# S111F.net
KiCad netlist of a schematic drawn in EAGLE
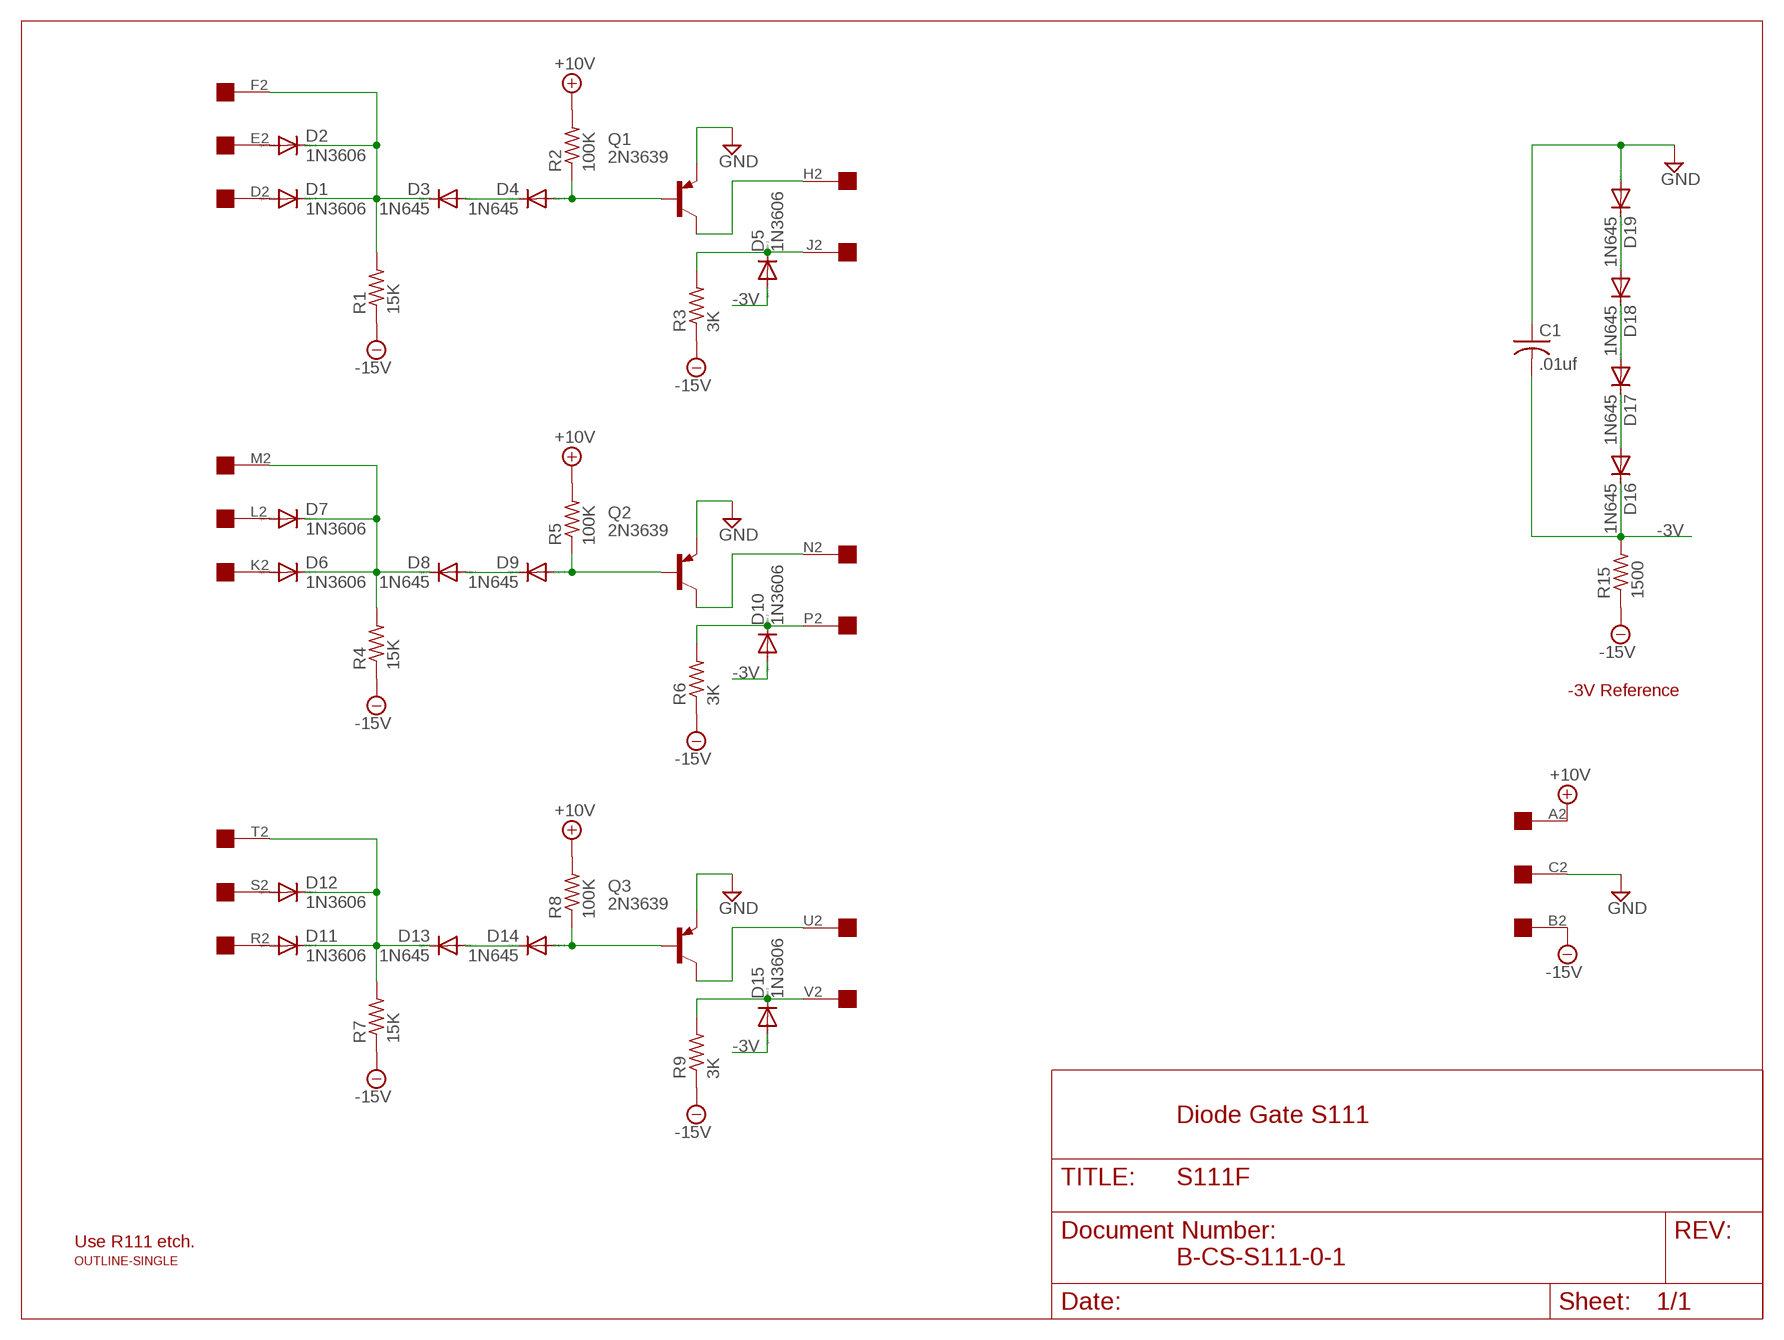
[diagram p0: schematic, sheet 1]

(export (version "E")
  (design (tool "Eeschema 10.0.6"))
  (components
    (comp (ref "C1")
      (value ".01uf")
      (footprint "eagle-import:C050-025X075")
      (libsource (lib "eagle-import") (part "C-US050-025X075"))
    )
    (comp (ref "D1")
      (value "1N3606")
      (footprint "eagle-import:DO35-10")
      (libsource (lib "eagle-import") (part "1N4148DO35-10"))
    )
    (comp (ref "D2")
      (value "1N3606")
      (footprint "eagle-import:DO35-10")
      (libsource (lib "eagle-import") (part "1N4148DO35-10"))
    )
    (comp (ref "D3")
      (value "1N645")
      (footprint "eagle-import:DO35-10")
      (libsource (lib "eagle-import") (part "1N4148DO35-10"))
    )
    (comp (ref "D4")
      (value "1N645")
      (footprint "eagle-import:DO35-10")
      (libsource (lib "eagle-import") (part "1N4148DO35-10"))
    )
    (comp (ref "D5")
      (value "1N3606")
      (footprint "eagle-import:DO35-10")
      (libsource (lib "eagle-import") (part "1N4148DO35-10"))
    )
    (comp (ref "D6")
      (value "1N3606")
      (footprint "eagle-import:DO35-10")
      (libsource (lib "eagle-import") (part "1N4148DO35-10"))
    )
    (comp (ref "D7")
      (value "1N3606")
      (footprint "eagle-import:DO35-10")
      (libsource (lib "eagle-import") (part "1N4148DO35-10"))
    )
    (comp (ref "D8")
      (value "1N645")
      (footprint "eagle-import:DO35-10")
      (libsource (lib "eagle-import") (part "1N4148DO35-10"))
    )
    (comp (ref "D9")
      (value "1N645")
      (footprint "eagle-import:DO35-10")
      (libsource (lib "eagle-import") (part "1N4148DO35-10"))
    )
    (comp (ref "D10")
      (value "1N3606")
      (footprint "eagle-import:DO35-10")
      (libsource (lib "eagle-import") (part "1N4148DO35-10"))
    )
    (comp (ref "D11")
      (value "1N3606")
      (footprint "eagle-import:DO35-10")
      (libsource (lib "eagle-import") (part "1N4148DO35-10"))
    )
    (comp (ref "D12")
      (value "1N3606")
      (footprint "eagle-import:DO35-10")
      (libsource (lib "eagle-import") (part "1N4148DO35-10"))
    )
    (comp (ref "D13")
      (value "1N645")
      (footprint "eagle-import:DO35-10")
      (libsource (lib "eagle-import") (part "1N4148DO35-10"))
    )
    (comp (ref "D14")
      (value "1N645")
      (footprint "eagle-import:DO35-10")
      (libsource (lib "eagle-import") (part "1N4148DO35-10"))
    )
    (comp (ref "D15")
      (value "1N3606")
      (footprint "eagle-import:DO35-10")
      (libsource (lib "eagle-import") (part "1N4148DO35-10"))
    )
    (comp (ref "D16")
      (value "1N645")
      (footprint "eagle-import:DO35-10")
      (libsource (lib "eagle-import") (part "1N4148DO35-10"))
    )
    (comp (ref "D17")
      (value "1N645")
      (footprint "eagle-import:DO35-10")
      (libsource (lib "eagle-import") (part "1N4148DO35-10"))
    )
    (comp (ref "D18")
      (value "1N645")
      (footprint "eagle-import:DO35-10")
      (libsource (lib "eagle-import") (part "1N4148DO35-10"))
    )
    (comp (ref "D19")
      (value "1N645")
      (footprint "eagle-import:DO35-10")
      (libsource (lib "eagle-import") (part "1N4148DO35-10"))
    )
    (comp (ref "Q1")
      (value "2N3639")
      (footprint "eagle-import:TO39")
      (libsource (lib "eagle-import") (part "2N3637"))
    )
    (comp (ref "Q2")
      (value "2N3639")
      (footprint "eagle-import:TO39")
      (libsource (lib "eagle-import") (part "2N3637"))
    )
    (comp (ref "Q3")
      (value "2N3639")
      (footprint "eagle-import:TO39")
      (libsource (lib "eagle-import") (part "2N3637"))
    )
    (comp (ref "R1")
      (value "15K")
      (footprint "eagle-import:0207_10")
      (libsource (lib "eagle-import") (part "R-US_0207/10"))
    )
    (comp (ref "R2")
      (value "100K")
      (footprint "eagle-import:0207_10")
      (libsource (lib "eagle-import") (part "R-US_0207/10"))
    )
    (comp (ref "R3")
      (value "3K")
      (footprint "eagle-import:0207_10")
      (libsource (lib "eagle-import") (part "R-US_0207/10"))
    )
    (comp (ref "R4")
      (value "15K")
      (footprint "eagle-import:0207_10")
      (libsource (lib "eagle-import") (part "R-US_0207/10"))
    )
    (comp (ref "R5")
      (value "100K")
      (footprint "eagle-import:0207_10")
      (libsource (lib "eagle-import") (part "R-US_0207/10"))
    )
    (comp (ref "R6")
      (value "3K")
      (footprint "eagle-import:0207_10")
      (libsource (lib "eagle-import") (part "R-US_0207/10"))
    )
    (comp (ref "R7")
      (value "15K")
      (footprint "eagle-import:0207_10")
      (libsource (lib "eagle-import") (part "R-US_0207/10"))
    )
    (comp (ref "R8")
      (value "100K")
      (footprint "eagle-import:0207_10")
      (libsource (lib "eagle-import") (part "R-US_0207/10"))
    )
    (comp (ref "R9")
      (value "3K")
      (footprint "eagle-import:0207_10")
      (libsource (lib "eagle-import") (part "R-US_0207/10"))
    )
    (comp (ref "R15")
      (value "1500")
      (footprint "eagle-import:0207_10")
      (libsource (lib "eagle-import") (part "R-US_0207/10"))
    )
    (comp (ref "U$1")
      (value "OUTLINE-SINGLE")
      (footprint "eagle-import:SINGLE")
      (libsource (lib "eagle-import") (part "OUTLINE-SINGLE"))
    )
    (comp (ref "U$2")
      (value "EDGE-1")
      (footprint "eagle-import:EDGE-CON1")
      (libsource (lib "eagle-import") (part "EDGE-1"))
    )
  )
  (nets
    (net (code "1") (name "+10V") (class "Default")
      (node (ref "R2") (pin "2") (pinfunction "2_2") (pintype "passive"))
      (node (ref "R5") (pin "2") (pinfunction "2_2") (pintype "passive"))
      (node (ref "R8") (pin "2") (pinfunction "2_2") (pintype "passive"))
      (node (ref "U$2") (pin "A2") (pinfunction "1_A2") (pintype "bidirectional"))
    )
    (net (code "2") (name "-15V") (class "Default")
      (node (ref "R1") (pin "1") (pinfunction "1_1") (pintype "passive"))
      (node (ref "R15") (pin "1") (pinfunction "1_1") (pintype "passive"))
      (node (ref "R3") (pin "1") (pinfunction "1_1") (pintype "passive"))
      (node (ref "R4") (pin "1") (pinfunction "1_1") (pintype "passive"))
      (node (ref "R6") (pin "1") (pinfunction "1_1") (pintype "passive"))
      (node (ref "R7") (pin "1") (pinfunction "1_1") (pintype "passive"))
      (node (ref "R9") (pin "1") (pinfunction "1_1") (pintype "passive"))
      (node (ref "U$2") (pin "B2") (pinfunction "1_B2") (pintype "bidirectional"))
    )
    (net (code "3") (name "/-3V") (class "Default")
      (node (ref "C1") (pin "2") (pinfunction "2_2") (pintype "passive"))
      (node (ref "D10") (pin "A") (pinfunction "A_A") (pintype "passive"))
      (node (ref "D15") (pin "A") (pinfunction "A_A") (pintype "passive"))
      (node (ref "D16") (pin "C") (pinfunction "C_C") (pintype "passive"))
      (node (ref "D5") (pin "A") (pinfunction "A_A") (pintype "passive"))
      (node (ref "R15") (pin "2") (pinfunction "2_2") (pintype "passive"))
    )
    (net (code "4") (name "GND") (class "Default")
      (node (ref "C1") (pin "1") (pinfunction "1_1") (pintype "passive"))
      (node (ref "D19") (pin "A") (pinfunction "A_A") (pintype "passive"))
      (node (ref "Q1") (pin "1") (pinfunction "E_1") (pintype "passive"))
      (node (ref "Q2") (pin "1") (pinfunction "E_1") (pintype "passive"))
      (node (ref "Q3") (pin "1") (pinfunction "E_1") (pintype "passive"))
      (node (ref "U$2") (pin "C2") (pinfunction "1_C2") (pintype "bidirectional"))
    )
    (net (code "5") (name "Net-(D3-PadA)") (class "Default")
      (node (ref "D3") (pin "A") (pinfunction "A_A") (pintype "passive"))
      (node (ref "D4") (pin "C") (pinfunction "C_C") (pintype "passive"))
    )
    (net (code "6") (name "Net-(D8-PadA)") (class "Default")
      (node (ref "D8") (pin "A") (pinfunction "A_A") (pintype "passive"))
      (node (ref "D9") (pin "C") (pinfunction "C_C") (pintype "passive"))
    )
    (net (code "7") (name "Net-(D13-PadA)") (class "Default")
      (node (ref "D13") (pin "A") (pinfunction "A_A") (pintype "passive"))
      (node (ref "D14") (pin "C") (pinfunction "C_C") (pintype "passive"))
    )
    (net (code "8") (name "Net-(D16-PadA)") (class "Default")
      (node (ref "D16") (pin "A") (pinfunction "A_A") (pintype "passive"))
      (node (ref "D17") (pin "C") (pinfunction "C_C") (pintype "passive"))
    )
    (net (code "9") (name "Net-(D17-PadA)") (class "Default")
      (node (ref "D17") (pin "A") (pinfunction "A_A") (pintype "passive"))
      (node (ref "D18") (pin "C") (pinfunction "C_C") (pintype "passive"))
    )
    (net (code "10") (name "Net-(D18-PadA)") (class "Default")
      (node (ref "D18") (pin "A") (pinfunction "A_A") (pintype "passive"))
      (node (ref "D19") (pin "C") (pinfunction "C_C") (pintype "passive"))
    )
    (net (code "11") (name "Net-(Q1-B)") (class "Default")
      (node (ref "D4") (pin "A") (pinfunction "A_A") (pintype "passive"))
      (node (ref "Q1") (pin "2") (pinfunction "B_2") (pintype "passive"))
      (node (ref "R2") (pin "1") (pinfunction "1_1") (pintype "passive"))
    )
    (net (code "12") (name "Net-(Q1-C)") (class "Default")
      (node (ref "Q1") (pin "3") (pinfunction "C_3") (pintype "passive"))
      (node (ref "U$2") (pin "H2") (pinfunction "1_H2") (pintype "bidirectional"))
    )
    (net (code "13") (name "Net-(Q2-B)") (class "Default")
      (node (ref "D9") (pin "A") (pinfunction "A_A") (pintype "passive"))
      (node (ref "Q2") (pin "2") (pinfunction "B_2") (pintype "passive"))
      (node (ref "R5") (pin "1") (pinfunction "1_1") (pintype "passive"))
    )
    (net (code "14") (name "Net-(Q2-C)") (class "Default")
      (node (ref "Q2") (pin "3") (pinfunction "C_3") (pintype "passive"))
      (node (ref "U$2") (pin "N2") (pinfunction "1_N2") (pintype "bidirectional"))
    )
    (net (code "15") (name "Net-(Q3-B)") (class "Default")
      (node (ref "D14") (pin "A") (pinfunction "A_A") (pintype "passive"))
      (node (ref "Q3") (pin "2") (pinfunction "B_2") (pintype "passive"))
      (node (ref "R8") (pin "1") (pinfunction "1_1") (pintype "passive"))
    )
    (net (code "16") (name "Net-(Q3-C)") (class "Default")
      (node (ref "Q3") (pin "3") (pinfunction "C_3") (pintype "passive"))
      (node (ref "U$2") (pin "U2") (pinfunction "1_U2") (pintype "bidirectional"))
    )
    (net (code "17") (name "Net-(U$2D-1)") (class "Default")
      (node (ref "D1") (pin "A") (pinfunction "A_A") (pintype "passive"))
      (node (ref "U$2") (pin "D2") (pinfunction "1_D2") (pintype "bidirectional"))
    )
    (net (code "18") (name "Net-(U$2E-1)") (class "Default")
      (node (ref "D2") (pin "A") (pinfunction "A_A") (pintype "passive"))
      (node (ref "U$2") (pin "E2") (pinfunction "1_E2") (pintype "bidirectional"))
    )
    (net (code "19") (name "Net-(U$2F-1)") (class "Default")
      (node (ref "D1") (pin "C") (pinfunction "C_C") (pintype "passive"))
      (node (ref "D2") (pin "C") (pinfunction "C_C") (pintype "passive"))
      (node (ref "D3") (pin "C") (pinfunction "C_C") (pintype "passive"))
      (node (ref "R1") (pin "2") (pinfunction "2_2") (pintype "passive"))
      (node (ref "U$2") (pin "F2") (pinfunction "1_F2") (pintype "bidirectional"))
    )
    (net (code "20") (name "Net-(U$2H-1)") (class "Default")
      (node (ref "D5") (pin "C") (pinfunction "C_C") (pintype "passive"))
      (node (ref "R3") (pin "2") (pinfunction "2_2") (pintype "passive"))
      (node (ref "U$2") (pin "J2") (pinfunction "1_J2") (pintype "bidirectional"))
    )
    (net (code "21") (name "Net-(U$2I-1)") (class "Default")
      (node (ref "D6") (pin "A") (pinfunction "A_A") (pintype "passive"))
      (node (ref "U$2") (pin "K2") (pinfunction "1_K2") (pintype "bidirectional"))
    )
    (net (code "22") (name "Net-(U$2J-1)") (class "Default")
      (node (ref "D7") (pin "A") (pinfunction "A_A") (pintype "passive"))
      (node (ref "U$2") (pin "L2") (pinfunction "1_L2") (pintype "bidirectional"))
    )
    (net (code "23") (name "Net-(U$2K-1)") (class "Default")
      (node (ref "D6") (pin "C") (pinfunction "C_C") (pintype "passive"))
      (node (ref "D7") (pin "C") (pinfunction "C_C") (pintype "passive"))
      (node (ref "D8") (pin "C") (pinfunction "C_C") (pintype "passive"))
      (node (ref "R4") (pin "2") (pinfunction "2_2") (pintype "passive"))
      (node (ref "U$2") (pin "M2") (pinfunction "1_M2") (pintype "bidirectional"))
    )
    (net (code "24") (name "Net-(U$2M-1)") (class "Default")
      (node (ref "D10") (pin "C") (pinfunction "C_C") (pintype "passive"))
      (node (ref "R6") (pin "2") (pinfunction "2_2") (pintype "passive"))
      (node (ref "U$2") (pin "P2") (pinfunction "1_P2") (pintype "bidirectional"))
    )
    (net (code "25") (name "Net-(U$2N-1)") (class "Default")
      (node (ref "D11") (pin "A") (pinfunction "A_A") (pintype "passive"))
      (node (ref "U$2") (pin "R2") (pinfunction "1_R2") (pintype "bidirectional"))
    )
    (net (code "26") (name "Net-(U$2O-1)") (class "Default")
      (node (ref "D12") (pin "A") (pinfunction "A_A") (pintype "passive"))
      (node (ref "U$2") (pin "S2") (pinfunction "1_S2") (pintype "bidirectional"))
    )
    (net (code "27") (name "Net-(U$2P-1)") (class "Default")
      (node (ref "D11") (pin "C") (pinfunction "C_C") (pintype "passive"))
      (node (ref "D12") (pin "C") (pinfunction "C_C") (pintype "passive"))
      (node (ref "D13") (pin "C") (pinfunction "C_C") (pintype "passive"))
      (node (ref "R7") (pin "2") (pinfunction "2_2") (pintype "passive"))
      (node (ref "U$2") (pin "T2") (pinfunction "1_T2") (pintype "bidirectional"))
    )
    (net (code "28") (name "Net-(U$2R-1)") (class "Default")
      (node (ref "D15") (pin "C") (pinfunction "C_C") (pintype "passive"))
      (node (ref "R9") (pin "2") (pinfunction "2_2") (pintype "passive"))
      (node (ref "U$2") (pin "V2") (pinfunction "1_V2") (pintype "bidirectional"))
    )
  )
)
